# shcematics.net
KiCad netlist of a schematic drawn in Altium Designer
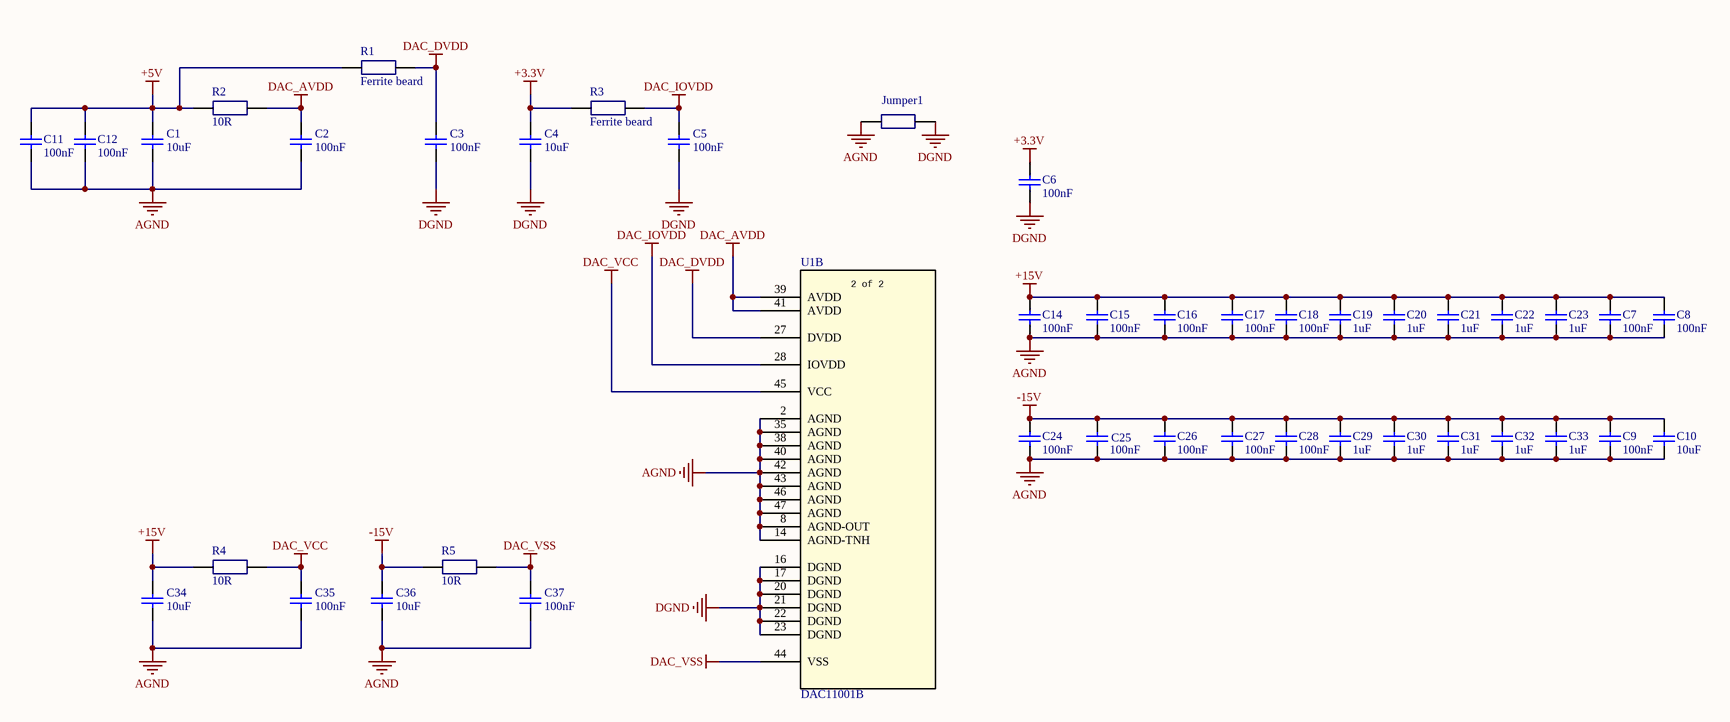
[diagram p0: shcematics.SchDoc]

(export (version "E")
  (design (tool "Eeschema 10.0.6"))
  (components
    (comp (ref "C1")
      (value "10uF")
      (footprint "CAP 0603")
      (description "Capacitor (Semiconductor SIM Model)")
      (fields (field (name "PUBLISHER") "Altium Limited"))
      (libsource (lib "Miscellaneous Devices") (part "Cap Semi"))
    )
    (comp (ref "C2")
      (value "100nF")
      (footprint "CAP 0603")
      (description "Capacitor (Semiconductor SIM Model)")
      (fields (field (name "PUBLISHER") "Altium Limited"))
      (libsource (lib "Miscellaneous Devices") (part "Cap Semi"))
    )
    (comp (ref "C3")
      (value "100nF")
      (footprint "CAP 0603")
      (description "Capacitor (Semiconductor SIM Model)")
      (fields (field (name "PUBLISHER") "Altium Limited"))
      (libsource (lib "Miscellaneous Devices") (part "Cap Semi"))
    )
    (comp (ref "C4")
      (value "10uF")
      (footprint "CAP 0603")
      (description "Capacitor (Semiconductor SIM Model)")
      (fields (field (name "PUBLISHER") "Altium Limited"))
      (libsource (lib "Miscellaneous Devices") (part "Cap Semi"))
    )
    (comp (ref "C5")
      (value "100nF")
      (footprint "CAP 0603")
      (description "Capacitor (Semiconductor SIM Model)")
      (fields (field (name "PUBLISHER") "Altium Limited"))
      (libsource (lib "Miscellaneous Devices") (part "Cap Semi"))
    )
    (comp (ref "C6")
      (value "100nF")
      (footprint "CAP 0603")
      (description "Capacitor (Semiconductor SIM Model)")
      (fields (field (name "PUBLISHER") "Altium Limited"))
      (libsource (lib "Miscellaneous Devices") (part "Cap Semi"))
    )
    (comp (ref "C7")
      (value "100nF")
      (footprint "CAP 0603")
      (description "Capacitor (Semiconductor SIM Model)")
      (fields (field (name "PUBLISHER") "Altium Limited"))
      (libsource (lib "Miscellaneous Devices") (part "Cap Semi"))
    )
    (comp (ref "C8")
      (value "100nF")
      (footprint "CAP 0603")
      (description "Capacitor (Semiconductor SIM Model)")
      (fields (field (name "PUBLISHER") "Altium Limited"))
      (libsource (lib "Miscellaneous Devices") (part "Cap Semi"))
    )
    (comp (ref "C9")
      (value "100nF")
      (footprint "CAP 0603")
      (description "Capacitor (Semiconductor SIM Model)")
      (fields (field (name "PUBLISHER") "Altium Limited"))
      (libsource (lib "Miscellaneous Devices") (part "Cap Semi"))
    )
    (comp (ref "C10")
      (value "10uF")
      (footprint "CAP 0603")
      (description "Capacitor (Semiconductor SIM Model)")
      (fields (field (name "PUBLISHER") "Altium Limited"))
      (libsource (lib "Miscellaneous Devices") (part "Cap Semi"))
    )
    (comp (ref "C11")
      (value "100nF")
      (footprint "CAP 0603")
      (description "Capacitor (Semiconductor SIM Model)")
      (fields (field (name "PUBLISHER") "Altium Limited"))
      (libsource (lib "Miscellaneous Devices") (part "Cap Semi"))
    )
    (comp (ref "C12")
      (value "100nF")
      (footprint "CAP 0603")
      (description "Capacitor (Semiconductor SIM Model)")
      (fields (field (name "PUBLISHER") "Altium Limited"))
      (libsource (lib "Miscellaneous Devices") (part "Cap Semi"))
    )
    (comp (ref "C14")
      (value "100nF")
      (footprint "CAP 0603")
      (description "Capacitor (Semiconductor SIM Model)")
      (fields (field (name "PUBLISHER") "Altium Limited"))
      (libsource (lib "Miscellaneous Devices") (part "Cap Semi"))
    )
    (comp (ref "C15")
      (value "100nF")
      (footprint "CAP 0603")
      (description "Capacitor (Semiconductor SIM Model)")
      (fields (field (name "PUBLISHER") "Altium Limited"))
      (libsource (lib "Miscellaneous Devices") (part "Cap Semi"))
    )
    (comp (ref "C16")
      (value "100nF")
      (footprint "CAP 0603")
      (description "Capacitor (Semiconductor SIM Model)")
      (fields (field (name "PUBLISHER") "Altium Limited"))
      (libsource (lib "Miscellaneous Devices") (part "Cap Semi"))
    )
    (comp (ref "C17")
      (value "100nF")
      (footprint "CAP 0603")
      (description "Capacitor (Semiconductor SIM Model)")
      (fields (field (name "PUBLISHER") "Altium Limited"))
      (libsource (lib "Miscellaneous Devices") (part "Cap Semi"))
    )
    (comp (ref "C18")
      (value "100nF")
      (footprint "CAP 0603")
      (description "Capacitor (Semiconductor SIM Model)")
      (fields (field (name "PUBLISHER") "Altium Limited"))
      (libsource (lib "Miscellaneous Devices") (part "Cap Semi"))
    )
    (comp (ref "C19")
      (value "1uF")
      (footprint "CAP 0603")
      (description "Capacitor (Semiconductor SIM Model)")
      (fields (field (name "PUBLISHER") "Altium Limited"))
      (libsource (lib "Miscellaneous Devices") (part "Cap Semi"))
    )
    (comp (ref "C20")
      (value "1uF")
      (footprint "CAP 0603")
      (description "Capacitor (Semiconductor SIM Model)")
      (fields (field (name "PUBLISHER") "Altium Limited"))
      (libsource (lib "Miscellaneous Devices") (part "Cap Semi"))
    )
    (comp (ref "C21")
      (value "1uF")
      (footprint "CAP 0603")
      (description "Capacitor (Semiconductor SIM Model)")
      (fields (field (name "PUBLISHER") "Altium Limited"))
      (libsource (lib "Miscellaneous Devices") (part "Cap Semi"))
    )
    (comp (ref "C22")
      (value "1uF")
      (footprint "CAP 0603")
      (description "Capacitor (Semiconductor SIM Model)")
      (fields (field (name "PUBLISHER") "Altium Limited"))
      (libsource (lib "Miscellaneous Devices") (part "Cap Semi"))
    )
    (comp (ref "C23")
      (value "1uF")
      (footprint "CAP 0603")
      (description "Capacitor (Semiconductor SIM Model)")
      (fields (field (name "PUBLISHER") "Altium Limited"))
      (libsource (lib "Miscellaneous Devices") (part "Cap Semi"))
    )
    (comp (ref "C24")
      (value "100nF")
      (footprint "CAP 0603")
      (description "Capacitor (Semiconductor SIM Model)")
      (fields (field (name "PUBLISHER") "Altium Limited"))
      (libsource (lib "Miscellaneous Devices") (part "Cap Semi"))
    )
    (comp (ref "C25")
      (value "100nF")
      (footprint "CAP 0603")
      (description "Capacitor (Semiconductor SIM Model)")
      (fields (field (name "PUBLISHER") "Altium Limited"))
      (libsource (lib "Miscellaneous Devices") (part "Cap Semi"))
    )
    (comp (ref "C26")
      (value "100nF")
      (footprint "CAP 0603")
      (description "Capacitor (Semiconductor SIM Model)")
      (fields (field (name "PUBLISHER") "Altium Limited"))
      (libsource (lib "Miscellaneous Devices") (part "Cap Semi"))
    )
    (comp (ref "C27")
      (value "100nF")
      (footprint "CAP 0603")
      (description "Capacitor (Semiconductor SIM Model)")
      (fields (field (name "PUBLISHER") "Altium Limited"))
      (libsource (lib "Miscellaneous Devices") (part "Cap Semi"))
    )
    (comp (ref "C28")
      (value "100nF")
      (footprint "CAP 0603")
      (description "Capacitor (Semiconductor SIM Model)")
      (fields (field (name "PUBLISHER") "Altium Limited"))
      (libsource (lib "Miscellaneous Devices") (part "Cap Semi"))
    )
    (comp (ref "C29")
      (value "1uF")
      (footprint "CAP 0603")
      (description "Capacitor (Semiconductor SIM Model)")
      (fields (field (name "PUBLISHER") "Altium Limited"))
      (libsource (lib "Miscellaneous Devices") (part "Cap Semi"))
    )
    (comp (ref "C30")
      (value "1uF")
      (footprint "CAP 0603")
      (description "Capacitor (Semiconductor SIM Model)")
      (fields (field (name "PUBLISHER") "Altium Limited"))
      (libsource (lib "Miscellaneous Devices") (part "Cap Semi"))
    )
    (comp (ref "C31")
      (value "1uF")
      (footprint "CAP 0603")
      (description "Capacitor (Semiconductor SIM Model)")
      (fields (field (name "PUBLISHER") "Altium Limited"))
      (libsource (lib "Miscellaneous Devices") (part "Cap Semi"))
    )
    (comp (ref "C32")
      (value "1uF")
      (footprint "CAP 0603")
      (description "Capacitor (Semiconductor SIM Model)")
      (fields (field (name "PUBLISHER") "Altium Limited"))
      (libsource (lib "Miscellaneous Devices") (part "Cap Semi"))
    )
    (comp (ref "C33")
      (value "1uF")
      (footprint "CAP 0603")
      (description "Capacitor (Semiconductor SIM Model)")
      (fields (field (name "PUBLISHER") "Altium Limited"))
      (libsource (lib "Miscellaneous Devices") (part "Cap Semi"))
    )
    (comp (ref "C34")
      (value "10uF")
      (footprint "C1206")
      (description "Capacitor (Semiconductor SIM Model)")
      (fields (field (name "PUBLISHER") "Altium Limited"))
      (libsource (lib "Miscellaneous Devices") (part "Cap Semi"))
    )
    (comp (ref "C35")
      (value "100nF")
      (footprint "CAP 0603")
      (description "Capacitor (Semiconductor SIM Model)")
      (fields (field (name "PUBLISHER") "Altium Limited"))
      (libsource (lib "Miscellaneous Devices") (part "Cap Semi"))
    )
    (comp (ref "C36")
      (value "10uF")
      (footprint "C1206")
      (description "Capacitor (Semiconductor SIM Model)")
      (fields (field (name "PUBLISHER") "Altium Limited"))
      (libsource (lib "Miscellaneous Devices") (part "Cap Semi"))
    )
    (comp (ref "C37")
      (value "100nF")
      (footprint "CAP 0603")
      (description "Capacitor (Semiconductor SIM Model)")
      (fields (field (name "PUBLISHER") "Altium Limited"))
      (libsource (lib "Miscellaneous Devices") (part "Cap Semi"))
    )
    (comp (ref "Jumper1")
      (value "~")
      (footprint "0402 jumper")
      (libsource (lib "Микрон-3") (part "Resistor 0805"))
    )
    (comp (ref "R1")
      (value "Ferrite beard")
      (footprint "CC1206JRNPOBBN100")
      (libsource (lib "Микрон-3") (part "Resistor 0805"))
    )
    (comp (ref "R2")
      (value "10R")
      (footprint "1608[0603]")
      (libsource (lib "Микрон-3") (part "Resistor 0805"))
    )
    (comp (ref "R3")
      (value "Ferrite beard")
      (footprint "CC1206JRNPOBBN100")
      (libsource (lib "Микрон-3") (part "Resistor 0805"))
    )
    (comp (ref "R4")
      (value "10R")
      (footprint "1608[0603]")
      (libsource (lib "Микрон-3") (part "Resistor 0805"))
    )
    (comp (ref "R5")
      (value "10R")
      (footprint "1608[0603]")
      (libsource (lib "Микрон-3") (part "Resistor 0805"))
    )
    (comp (ref "U1")
      (value "DAC11001B")
      (footprint "QFP_APFBR_TEX")
      (description "No Description Available")
      (fields
        (field (name "MANUFACTURER_PART_NUMBER") "DAC11001APFBR")
        (field (name "COPYRIGHT") "Copyright (C) 2018 Accelerated Designs. All rights reserved")
      )
      (libsource (lib "2021-01-15_13-58-29") (part "DAC11001APFBR"))
    )
  )
  (nets
    (net (code "1") (name "+3.3V") (class "Default")
      (node (ref "C4") (pin "1") (pinfunction "1_1") (pintype "passive"))
      (node (ref "C6") (pin "2") (pinfunction "2_2") (pintype "passive"))
      (node (ref "R3") (pin "2") (pinfunction "2_2") (pintype "passive"))
    )
    (net (code "2") (name "+5V") (class "Default")
      (node (ref "C1") (pin "1") (pinfunction "1_1") (pintype "passive"))
      (node (ref "C11") (pin "2") (pinfunction "2_2") (pintype "passive"))
      (node (ref "C12") (pin "2") (pinfunction "2_2") (pintype "passive"))
      (node (ref "R1") (pin "2") (pinfunction "2_2") (pintype "passive"))
      (node (ref "R2") (pin "2") (pinfunction "2_2") (pintype "passive"))
    )
    (net (code "3") (name "+15V") (class "Default")
      (node (ref "C14") (pin "2") (pinfunction "2_2") (pintype "passive"))
      (node (ref "C15") (pin "2") (pinfunction "2_2") (pintype "passive"))
      (node (ref "C16") (pin "2") (pinfunction "2_2") (pintype "passive"))
      (node (ref "C17") (pin "2") (pinfunction "2_2") (pintype "passive"))
      (node (ref "C18") (pin "2") (pinfunction "2_2") (pintype "passive"))
      (node (ref "C19") (pin "2") (pinfunction "2_2") (pintype "passive"))
      (node (ref "C20") (pin "2") (pinfunction "2_2") (pintype "passive"))
      (node (ref "C21") (pin "2") (pinfunction "2_2") (pintype "passive"))
      (node (ref "C22") (pin "2") (pinfunction "2_2") (pintype "passive"))
      (node (ref "C23") (pin "2") (pinfunction "2_2") (pintype "passive"))
      (node (ref "C34") (pin "1") (pinfunction "1_1") (pintype "passive"))
      (node (ref "C7") (pin "2") (pinfunction "2_2") (pintype "passive"))
      (node (ref "C8") (pin "2") (pinfunction "2_2") (pintype "passive"))
      (node (ref "R4") (pin "2") (pinfunction "2_2") (pintype "passive"))
    )
    (net (code "4") (name "-15V") (class "Default")
      (node (ref "C10") (pin "2") (pinfunction "2_2") (pintype "passive"))
      (node (ref "C24") (pin "2") (pinfunction "2_2") (pintype "passive"))
      (node (ref "C25") (pin "2") (pinfunction "2_2") (pintype "passive"))
      (node (ref "C26") (pin "2") (pinfunction "2_2") (pintype "passive"))
      (node (ref "C27") (pin "2") (pinfunction "2_2") (pintype "passive"))
      (node (ref "C28") (pin "2") (pinfunction "2_2") (pintype "passive"))
      (node (ref "C29") (pin "2") (pinfunction "2_2") (pintype "passive"))
      (node (ref "C30") (pin "2") (pinfunction "2_2") (pintype "passive"))
      (node (ref "C31") (pin "2") (pinfunction "2_2") (pintype "passive"))
      (node (ref "C32") (pin "2") (pinfunction "2_2") (pintype "passive"))
      (node (ref "C33") (pin "2") (pinfunction "2_2") (pintype "passive"))
      (node (ref "C36") (pin "1") (pinfunction "1_1") (pintype "passive"))
      (node (ref "C9") (pin "2") (pinfunction "2_2") (pintype "passive"))
      (node (ref "R5") (pin "2") (pinfunction "2_2") (pintype "passive"))
    )
    (net (code "5") (name "AGND") (class "Default")
      (node (ref "C1") (pin "2") (pinfunction "2_2") (pintype "passive"))
      (node (ref "C10") (pin "1") (pinfunction "1_1") (pintype "passive"))
      (node (ref "C11") (pin "1") (pinfunction "1_1") (pintype "passive"))
      (node (ref "C12") (pin "1") (pinfunction "1_1") (pintype "passive"))
      (node (ref "C14") (pin "1") (pinfunction "1_1") (pintype "passive"))
      (node (ref "C15") (pin "1") (pinfunction "1_1") (pintype "passive"))
      (node (ref "C16") (pin "1") (pinfunction "1_1") (pintype "passive"))
      (node (ref "C17") (pin "1") (pinfunction "1_1") (pintype "passive"))
      (node (ref "C18") (pin "1") (pinfunction "1_1") (pintype "passive"))
      (node (ref "C19") (pin "1") (pinfunction "1_1") (pintype "passive"))
      (node (ref "C2") (pin "2") (pinfunction "2_2") (pintype "passive"))
      (node (ref "C20") (pin "1") (pinfunction "1_1") (pintype "passive"))
      (node (ref "C21") (pin "1") (pinfunction "1_1") (pintype "passive"))
      (node (ref "C22") (pin "1") (pinfunction "1_1") (pintype "passive"))
      (node (ref "C23") (pin "1") (pinfunction "1_1") (pintype "passive"))
      (node (ref "C24") (pin "1") (pinfunction "1_1") (pintype "passive"))
      (node (ref "C25") (pin "1") (pinfunction "1_1") (pintype "passive"))
      (node (ref "C26") (pin "1") (pinfunction "1_1") (pintype "passive"))
      (node (ref "C27") (pin "1") (pinfunction "1_1") (pintype "passive"))
      (node (ref "C28") (pin "1") (pinfunction "1_1") (pintype "passive"))
      (node (ref "C29") (pin "1") (pinfunction "1_1") (pintype "passive"))
      (node (ref "C30") (pin "1") (pinfunction "1_1") (pintype "passive"))
      (node (ref "C31") (pin "1") (pinfunction "1_1") (pintype "passive"))
      (node (ref "C32") (pin "1") (pinfunction "1_1") (pintype "passive"))
      (node (ref "C33") (pin "1") (pinfunction "1_1") (pintype "passive"))
      (node (ref "C34") (pin "2") (pinfunction "2_2") (pintype "passive"))
      (node (ref "C35") (pin "2") (pinfunction "2_2") (pintype "passive"))
      (node (ref "C36") (pin "2") (pinfunction "2_2") (pintype "passive"))
      (node (ref "C37") (pin "2") (pinfunction "2_2") (pintype "passive"))
      (node (ref "C7") (pin "1") (pinfunction "1_1") (pintype "passive"))
      (node (ref "C8") (pin "1") (pinfunction "1_1") (pintype "passive"))
      (node (ref "C9") (pin "1") (pinfunction "1_1") (pintype "passive"))
      (node (ref "Jumper1") (pin "2") (pinfunction "2_2") (pintype "passive"))
      (node (ref "U1") (pin "14") (pinfunction "AGND-TNH_14") (pintype "passive"))
      (node (ref "U1") (pin "2") (pinfunction "AGND_2") (pintype "passive"))
      (node (ref "U1") (pin "35") (pinfunction "AGND_35") (pintype "passive"))
      (node (ref "U1") (pin "38") (pinfunction "AGND_38") (pintype "passive"))
      (node (ref "U1") (pin "40") (pinfunction "AGND_40") (pintype "passive"))
      (node (ref "U1") (pin "42") (pinfunction "AGND_42") (pintype "passive"))
      (node (ref "U1") (pin "43") (pinfunction "AGND_43") (pintype "passive"))
      (node (ref "U1") (pin "46") (pinfunction "AGND_46") (pintype "passive"))
      (node (ref "U1") (pin "47") (pinfunction "AGND_47") (pintype "passive"))
      (node (ref "U1") (pin "8") (pinfunction "AGND-OUT_8") (pintype "passive"))
    )
    (net (code "6") (name "DAC_AVDD") (class "Default")
      (node (ref "C2") (pin "1") (pinfunction "1_1") (pintype "passive"))
      (node (ref "R2") (pin "1") (pinfunction "A_1") (pintype "passive"))
      (node (ref "U1") (pin "39") (pinfunction "AVDD_39") (pintype "power_in"))
      (node (ref "U1") (pin "41") (pinfunction "AVDD_41") (pintype "power_in"))
    )
    (net (code "7") (name "DAC_DVDD") (class "Default")
      (node (ref "C3") (pin "1") (pinfunction "1_1") (pintype "passive"))
      (node (ref "R1") (pin "1") (pinfunction "A_1") (pintype "passive"))
      (node (ref "U1") (pin "27") (pinfunction "DVDD_27") (pintype "power_in"))
    )
    (net (code "8") (name "DAC_IOVDD") (class "Default")
      (node (ref "C5") (pin "1") (pinfunction "1_1") (pintype "passive"))
      (node (ref "R3") (pin "1") (pinfunction "A_1") (pintype "passive"))
      (node (ref "U1") (pin "28") (pinfunction "IOVDD_28") (pintype "power_in"))
    )
    (net (code "9") (name "DAC_VCC") (class "Default")
      (node (ref "C35") (pin "1") (pinfunction "1_1") (pintype "passive"))
      (node (ref "R4") (pin "1") (pinfunction "A_1") (pintype "passive"))
      (node (ref "U1") (pin "45") (pinfunction "VCC_45") (pintype "power_in"))
    )
    (net (code "10") (name "DAC_VSS") (class "Default")
      (node (ref "C37") (pin "1") (pinfunction "1_1") (pintype "passive"))
      (node (ref "R5") (pin "1") (pinfunction "A_1") (pintype "passive"))
      (node (ref "U1") (pin "44") (pinfunction "VSS_44") (pintype "passive"))
    )
    (net (code "11") (name "DGND") (class "Default")
      (node (ref "C3") (pin "2") (pinfunction "2_2") (pintype "passive"))
      (node (ref "C4") (pin "2") (pinfunction "2_2") (pintype "passive"))
      (node (ref "C5") (pin "2") (pinfunction "2_2") (pintype "passive"))
      (node (ref "C6") (pin "1") (pinfunction "1_1") (pintype "passive"))
      (node (ref "Jumper1") (pin "1") (pinfunction "A_1") (pintype "passive"))
      (node (ref "U1") (pin "16") (pinfunction "DGND_16") (pintype "passive"))
      (node (ref "U1") (pin "17") (pinfunction "DGND_17") (pintype "passive"))
      (node (ref "U1") (pin "20") (pinfunction "DGND_20") (pintype "passive"))
      (node (ref "U1") (pin "21") (pinfunction "DGND_21") (pintype "passive"))
      (node (ref "U1") (pin "22") (pinfunction "DGND_22") (pintype "passive"))
      (node (ref "U1") (pin "23") (pinfunction "DGND_23") (pintype "passive"))
    )
  )
)
